# CON_MIDI_DIN5.net
KiCad netlist of a schematic drawn in Altium Designer
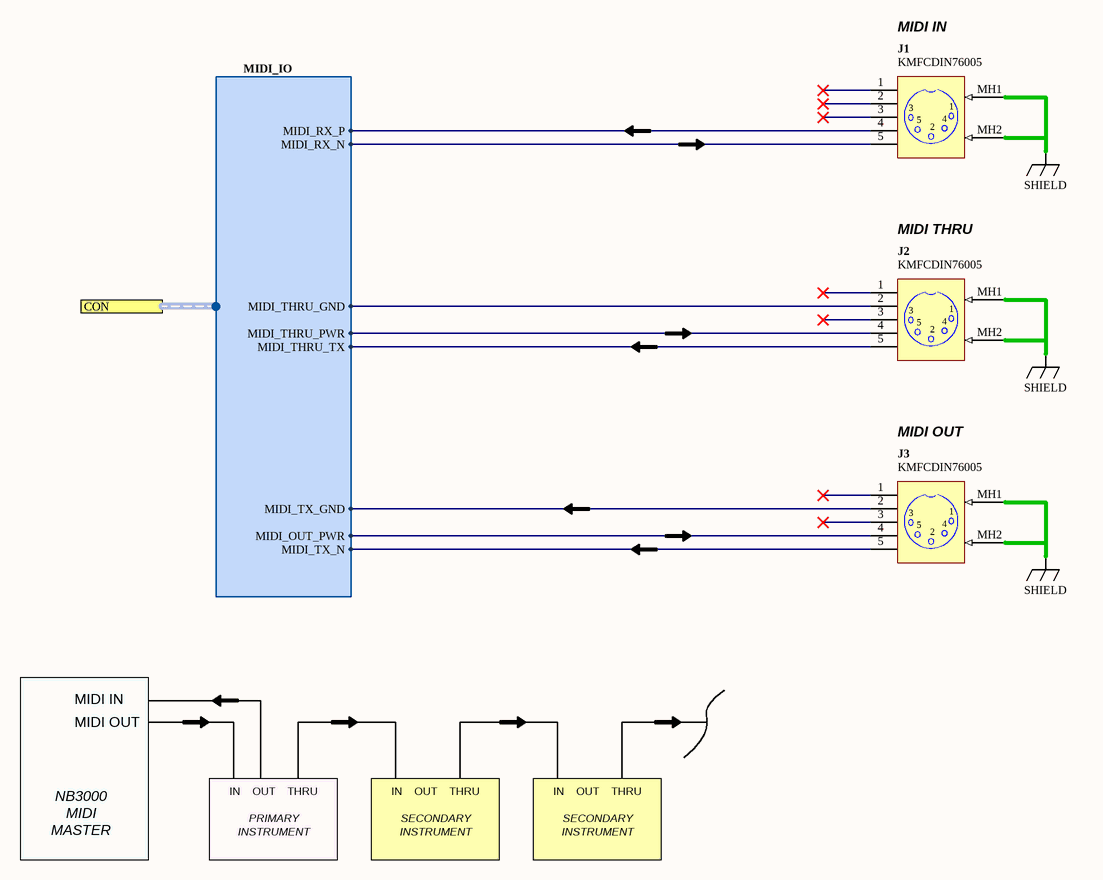
[diagram p0: CON_MIDI_DIN5.SCHDOC]

(export (version "E")
  (design (tool "Eeschema 10.0.6"))
  (components
    (comp (ref "J1")
      (value "KMFCDIN76005")
      (footprint "KMFCDIN76005")
      (description "Socket, 5-way R/A DIN")
      (libsource (lib "AltiumDesignLibrary") (part "KMFCDIN76005"))
    )
    (comp (ref "J2")
      (value "KMFCDIN76005")
      (footprint "KMFCDIN76005")
      (description "Socket, 5-way R/A DIN")
      (libsource (lib "AltiumDesignLibrary") (part "KMFCDIN76005"))
    )
    (comp (ref "J3")
      (value "KMFCDIN76005")
      (footprint "KMFCDIN76005")
      (description "Socket, 5-way R/A DIN")
      (libsource (lib "AltiumDesignLibrary") (part "KMFCDIN76005"))
    )
  )
  (nets
    (net (code "2") (name "/MIDI_OUT_PWR") (class "Default")
      (node (ref "J3") (pin "4") (pinfunction "4_4") (pintype "passive"))
    )
    (net (code "3") (name "/MIDI_RX_N") (class "Default")
      (node (ref "J1") (pin "5") (pinfunction "5_5") (pintype "passive"))
    )
    (net (code "4") (name "/MIDI_RX_P") (class "Default")
      (node (ref "J1") (pin "4") (pinfunction "4_4") (pintype "passive"))
    )
    (net (code "5") (name "/MIDI_THRU_GND") (class "Default")
      (node (ref "J2") (pin "2") (pinfunction "2_2") (pintype "passive"))
    )
    (net (code "6") (name "/MIDI_THRU_PWR") (class "Default")
      (node (ref "J2") (pin "4") (pinfunction "4_4") (pintype "passive"))
    )
    (net (code "7") (name "/MIDI_THRU_TX") (class "Default")
      (node (ref "J2") (pin "5") (pinfunction "5_5") (pintype "passive"))
    )
    (net (code "8") (name "/MIDI_TX_GND") (class "Default")
      (node (ref "J3") (pin "2") (pinfunction "2_2") (pintype "passive"))
    )
    (net (code "9") (name "/MIDI_TX_N") (class "Default")
      (node (ref "J3") (pin "5") (pinfunction "5_5") (pintype "passive"))
    )
    (net (code "11") (name "SHIELD") (class "Default")
      (node (ref "J1") (pin "MH1") (pinfunction "MH1_MH1") (pintype "input"))
      (node (ref "J1") (pin "MH2") (pinfunction "MH2_MH2") (pintype "input"))
      (node (ref "J2") (pin "MH1") (pinfunction "MH1_MH1") (pintype "input"))
      (node (ref "J2") (pin "MH2") (pinfunction "MH2_MH2") (pintype "input"))
      (node (ref "J3") (pin "MH1") (pinfunction "MH1_MH1") (pintype "input"))
      (node (ref "J3") (pin "MH2") (pinfunction "MH2_MH2") (pintype "input"))
    )
    (net (code "12") (name "unconnected-(J1-Pad1)") (class "Default")
      (node (ref "J1") (pin "1") (pinfunction "1_1") (pintype "passive+no_connect"))
    )
    (net (code "13") (name "unconnected-(J1-Pad2)") (class "Default")
      (node (ref "J1") (pin "2") (pinfunction "2_2") (pintype "passive+no_connect"))
    )
    (net (code "14") (name "unconnected-(J1-Pad3)") (class "Default")
      (node (ref "J1") (pin "3") (pinfunction "3_3") (pintype "passive+no_connect"))
    )
    (net (code "15") (name "unconnected-(J2-Pad1)") (class "Default")
      (node (ref "J2") (pin "1") (pinfunction "1_1") (pintype "passive+no_connect"))
    )
    (net (code "16") (name "unconnected-(J2-Pad3)") (class "Default")
      (node (ref "J2") (pin "3") (pinfunction "3_3") (pintype "passive+no_connect"))
    )
    (net (code "17") (name "unconnected-(J3-Pad1)") (class "Default")
      (node (ref "J3") (pin "1") (pinfunction "1_1") (pintype "passive+no_connect"))
    )
    (net (code "18") (name "unconnected-(J3-Pad3)") (class "Default")
      (node (ref "J3") (pin "3") (pinfunction "3_3") (pintype "passive+no_connect"))
    )
  )
)
